# ATmega328p-DHT11-DS1307-LCD-StripBd.net
KiCad netlist of a schematic drawn in EAGLE
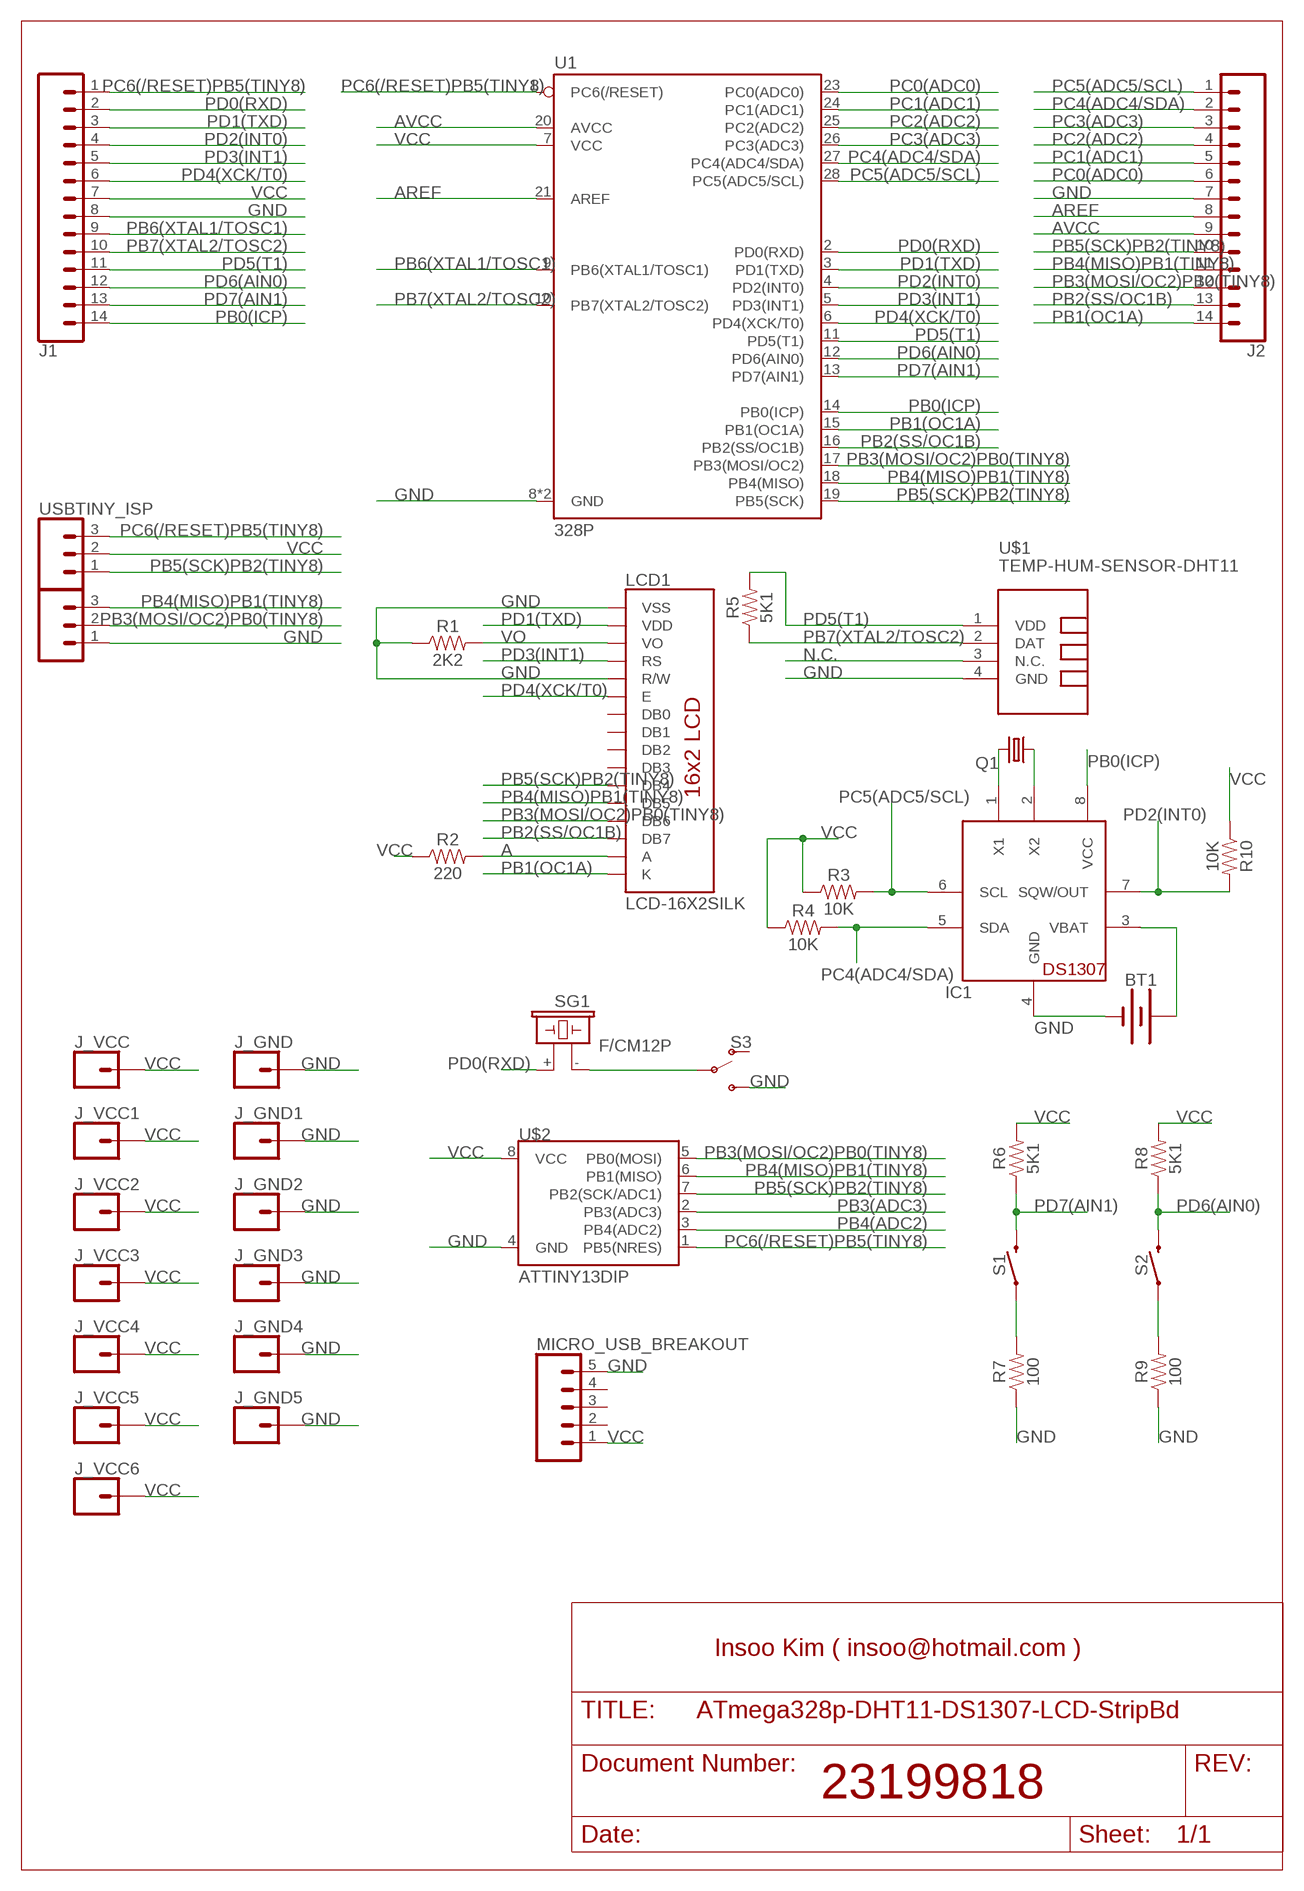
[diagram p0: schematic, sheet 1]

(export (version "E")
  (design (tool "Eeschema 10.0.6"))
  (components
    (comp (ref "BT1")
      (value "BATTERY-20MM_PTH")
      (footprint "eagle-import:BATTCOM_20MM_PTH")
      (libsource (lib "eagle-import") (part "BATTERY-20MM_PTH"))
    )
    (comp (ref "IC1")
      (value "DS1307")
      (footprint "eagle-import:DIL08")
      (libsource (lib "eagle-import") (part "DS1307"))
    )
    (comp (ref "J1")
      (value "CONN_14")
      (footprint "eagle-import:1X14")
      (libsource (lib "eagle-import") (part "CONN_14"))
    )
    (comp (ref "J2")
      (value "CONN_14")
      (footprint "eagle-import:1X14")
      (libsource (lib "eagle-import") (part "CONN_14"))
    )
    (comp (ref "J3")
      (value "455-1750-1-ND")
      (footprint "eagle-import:1X03")
      (libsource (lib "eagle-import") (part "CONN_03"))
    )
    (comp (ref "J_GND")
      (value "CONN_01")
      (footprint "eagle-import:1X01")
      (libsource (lib "eagle-import") (part "CONN_01"))
    )
    (comp (ref "J_GND1")
      (value "CONN_01")
      (footprint "eagle-import:1X01")
      (libsource (lib "eagle-import") (part "CONN_01"))
    )
    (comp (ref "J_GND2")
      (value "CONN_01")
      (footprint "eagle-import:1X01")
      (libsource (lib "eagle-import") (part "CONN_01"))
    )
    (comp (ref "J_GND3")
      (value "CONN_01")
      (footprint "eagle-import:1X01")
      (libsource (lib "eagle-import") (part "CONN_01"))
    )
    (comp (ref "J_GND4")
      (value "CONN_01")
      (footprint "eagle-import:1X01")
      (libsource (lib "eagle-import") (part "CONN_01"))
    )
    (comp (ref "J_GND5")
      (value "CONN_01")
      (footprint "eagle-import:1X01")
      (libsource (lib "eagle-import") (part "CONN_01"))
    )
    (comp (ref "J_VCC")
      (value "CONN_01")
      (footprint "eagle-import:1X01")
      (libsource (lib "eagle-import") (part "CONN_01"))
    )
    (comp (ref "J_VCC1")
      (value "CONN_01")
      (footprint "eagle-import:1X01")
      (libsource (lib "eagle-import") (part "CONN_01"))
    )
    (comp (ref "J_VCC2")
      (value "CONN_01")
      (footprint "eagle-import:1X01")
      (libsource (lib "eagle-import") (part "CONN_01"))
    )
    (comp (ref "J_VCC3")
      (value "CONN_01")
      (footprint "eagle-import:1X01")
      (libsource (lib "eagle-import") (part "CONN_01"))
    )
    (comp (ref "J_VCC4")
      (value "CONN_01")
      (footprint "eagle-import:1X01")
      (libsource (lib "eagle-import") (part "CONN_01"))
    )
    (comp (ref "J_VCC5")
      (value "CONN_01")
      (footprint "eagle-import:1X01")
      (libsource (lib "eagle-import") (part "CONN_01"))
    )
    (comp (ref "J_VCC6")
      (value "CONN_01")
      (footprint "eagle-import:1X01")
      (libsource (lib "eagle-import") (part "CONN_01"))
    )
    (comp (ref "LCD1")
      (value "LCD-16X2SILK")
      (footprint "eagle-import:LCD-16X2")
      (libsource (lib "eagle-import") (part "LCD-16X2SILK"))
    )
    (comp (ref "MICRO_USB_BREAKOUT")
      (value "CONN_05")
      (footprint "eagle-import:1X05")
      (libsource (lib "eagle-import") (part "CONN_05"))
    )
    (comp (ref "Q1")
      (value "CRYSTALTC26H")
      (footprint "eagle-import:TC26H")
      (libsource (lib "eagle-import") (part "CRYSTALTC26H"))
    )
    (comp (ref "R1")
      (value "2K2")
      (footprint "eagle-import:AXIAL-0.3")
      (libsource (lib "eagle-import") (part "1KOHM-HORIZ-1/4W-5%"))
    )
    (comp (ref "R2")
      (value "220")
      (footprint "eagle-import:AXIAL-0.3")
      (libsource (lib "eagle-import") (part "1KOHM-HORIZ-1/4W-5%"))
    )
    (comp (ref "R3")
      (value "10K")
      (footprint "eagle-import:AXIAL-0.3")
      (libsource (lib "eagle-import") (part "1KOHM-HORIZ-1/4W-5%"))
    )
    (comp (ref "R4")
      (value "10K")
      (footprint "eagle-import:AXIAL-0.3")
      (libsource (lib "eagle-import") (part "1KOHM-HORIZ-1/4W-5%"))
    )
    (comp (ref "R5")
      (value "5K1")
      (footprint "eagle-import:AXIAL-0.3")
      (libsource (lib "eagle-import") (part "1KOHM-HORIZ-1/4W-5%"))
    )
    (comp (ref "R6")
      (value "5K1")
      (footprint "eagle-import:AXIAL-0.3")
      (libsource (lib "eagle-import") (part "1KOHM-HORIZ-1/4W-5%"))
    )
    (comp (ref "R7")
      (value "100")
      (footprint "eagle-import:AXIAL-0.3")
      (libsource (lib "eagle-import") (part "1KOHM-HORIZ-1/4W-5%"))
    )
    (comp (ref "R8")
      (value "5K1")
      (footprint "eagle-import:AXIAL-0.3")
      (libsource (lib "eagle-import") (part "1KOHM-HORIZ-1/4W-5%"))
    )
    (comp (ref "R9")
      (value "100")
      (footprint "eagle-import:AXIAL-0.3")
      (libsource (lib "eagle-import") (part "1KOHM-HORIZ-1/4W-5%"))
    )
    (comp (ref "R10")
      (value "10K")
      (footprint "eagle-import:AXIAL-0.3")
      (libsource (lib "eagle-import") (part "1KOHM-HORIZ-1/4W-5%"))
    )
    (comp (ref "S1")
      (value "MOMENTARY-SWITCH-SPST-PTH-12MM")
      (footprint "eagle-import:TACTILE_SWITCH_PTH_12MM")
      (libsource (lib "eagle-import") (part "MOMENTARY-SWITCH-SPST-PTH-12MM"))
    )
    (comp (ref "S2")
      (value "MOMENTARY-SWITCH-SPST-PTH-12MM")
      (footprint "eagle-import:TACTILE_SWITCH_PTH_12MM")
      (libsource (lib "eagle-import") (part "MOMENTARY-SWITCH-SPST-PTH-12MM"))
    )
    (comp (ref "S3")
      (value "SWITCH-SPDT-PTH-11.6X4.0MM")
      (footprint "eagle-import:SWITCH_SPDT_PTH_11.6X4.0MM")
      (libsource (lib "eagle-import") (part "SWITCH-SPDT-PTH-11.6X4.0MM"))
    )
    (comp (ref "SG1")
      (value "F/CM12P")
      (footprint "eagle-import:F_CM12P")
      (libsource (lib "eagle-import") (part "F/CM12P"))
    )
    (comp (ref "U$1")
      (value "TEMP-HUM-SENSOR-DHT11")
      (footprint "eagle-import:TEMP-HUM-SENSOR-DHT11")
      (libsource (lib "eagle-import") (part "TEMP-HUM-SENSOR-DHT11"))
    )
    (comp (ref "U$2")
      (value "ATTINY13DIP")
      (footprint "eagle-import:DIP08_MCU")
      (libsource (lib "eagle-import") (part "ATTINY13DIP"))
    )
    (comp (ref "U1")
      (value "328P")
      (footprint "eagle-import:DIP28")
      (libsource (lib "eagle-import") (part "ATMEGA328P_PDIP"))
    )
    (comp (ref "USBTINY_ISP")
      (value "455-1750-1-ND")
      (footprint "eagle-import:1X03")
      (libsource (lib "eagle-import") (part "CONN_03"))
    )
  )
  (nets
    (net (code "1") (name "/A") (class "Default")
      (node (ref "LCD1") (pin "15") (pinfunction "A_15") (pintype "power_in"))
      (node (ref "R2") (pin "P$2") (pinfunction "2_P$2") (pintype "passive"))
    )
    (net (code "2") (name "/AREF") (class "Default")
      (node (ref "J2") (pin "8") (pinfunction "8_8") (pintype "passive"))
      (node (ref "U1") (pin "21") (pinfunction "AREF_21") (pintype "bidirectional"))
    )
    (net (code "3") (name "/AVCC") (class "Default")
      (node (ref "J2") (pin "9") (pinfunction "9_9") (pintype "passive"))
      (node (ref "U1") (pin "20") (pinfunction "AVCC_20") (pintype "bidirectional"))
    )
    (net (code "4") (name "/GND") (class "Default")
      (node (ref "BT1") (pin "2") (pinfunction "-_2") (pintype "power_in"))
      (node (ref "IC1") (pin "4") (pinfunction "GND_4") (pintype "power_in"))
      (node (ref "J1") (pin "8") (pinfunction "8_8") (pintype "passive"))
      (node (ref "J2") (pin "7") (pinfunction "7_7") (pintype "passive"))
      (node (ref "J3") (pin "1") (pinfunction "1_1") (pintype "passive"))
      (node (ref "J_GND") (pin "1") (pinfunction "1_1") (pintype "passive"))
      (node (ref "J_GND1") (pin "1") (pinfunction "1_1") (pintype "passive"))
      (node (ref "J_GND2") (pin "1") (pinfunction "1_1") (pintype "passive"))
      (node (ref "J_GND3") (pin "1") (pinfunction "1_1") (pintype "passive"))
      (node (ref "J_GND4") (pin "1") (pinfunction "1_1") (pintype "passive"))
      (node (ref "J_GND5") (pin "1") (pinfunction "1_1") (pintype "passive"))
      (node (ref "LCD1") (pin "1") (pinfunction "VSS_1") (pintype "power_in"))
      (node (ref "LCD1") (pin "5") (pinfunction "R/W_5") (pintype "input"))
      (node (ref "MICRO_USB_BREAKOUT") (pin "5") (pinfunction "5_5") (pintype "passive"))
      (node (ref "R1") (pin "P$1") (pinfunction "1_P$1") (pintype "passive"))
      (node (ref "R7") (pin "P$1") (pinfunction "1_P$1") (pintype "passive"))
      (node (ref "R9") (pin "P$1") (pinfunction "1_P$1") (pintype "passive"))
      (node (ref "S3") (pin "3") (pinfunction "S_3") (pintype "passive"))
      (node (ref "U$1") (pin "4") (pinfunction "GND_4") (pintype "power_in"))
      (node (ref "U$2") (pin "4") (pinfunction "GND_4") (pintype "bidirectional"))
      (node (ref "U1") (pin "22") (pinfunction "GND_22") (pintype "bidirectional"))
      (node (ref "U1") (pin "8") (pinfunction "GND_8") (pintype "bidirectional"))
    )
    (net (code "5") (name "/N.C.") (class "Default")
      (node (ref "U$1") (pin "3") (pinfunction "N.C._3") (pintype "passive"))
    )
    (net (code "6") (name "/PB0(ICP)") (class "Default")
      (node (ref "IC1") (pin "8") (pinfunction "VCC_8") (pintype "power_in"))
      (node (ref "J1") (pin "14") (pinfunction "14_14") (pintype "passive"))
      (node (ref "U1") (pin "14") (pinfunction "PB0(ICP)_14") (pintype "bidirectional"))
    )
    (net (code "7") (name "/PB1(OC1A)") (class "Default")
      (node (ref "J2") (pin "14") (pinfunction "14_14") (pintype "passive"))
      (node (ref "LCD1") (pin "16") (pinfunction "K_16") (pintype "power_in"))
      (node (ref "U1") (pin "15") (pinfunction "PB1(OC1A)_15") (pintype "bidirectional"))
    )
    (net (code "8") (name "/PB2(SS{slash}OC1B)") (class "Default")
      (node (ref "J2") (pin "13") (pinfunction "13_13") (pintype "passive"))
      (node (ref "LCD1") (pin "14") (pinfunction "DB7_14") (pintype "bidirectional"))
      (node (ref "U1") (pin "16") (pinfunction "PB2(SS/OC1B)_16") (pintype "bidirectional"))
    )
    (net (code "9") (name "/PB3(ADC3)") (class "Default")
      (node (ref "U$2") (pin "2") (pinfunction "PB3(ADC3)_2") (pintype "bidirectional"))
    )
    (net (code "10") (name "/PB3(MOSI{slash}OC2)PB0(TINY8)") (class "Default")
      (node (ref "J2") (pin "12") (pinfunction "12_12") (pintype "passive"))
      (node (ref "J3") (pin "2") (pinfunction "2_2") (pintype "passive"))
      (node (ref "LCD1") (pin "13") (pinfunction "DB6_13") (pintype "bidirectional"))
      (node (ref "U$2") (pin "5") (pinfunction "PB0(MOSI)_5") (pintype "bidirectional"))
      (node (ref "U1") (pin "17") (pinfunction "PB3(MOSI/OC2)_17") (pintype "bidirectional"))
    )
    (net (code "11") (name "/PB4(ADC2)") (class "Default")
      (node (ref "U$2") (pin "3") (pinfunction "PB4(ADC2)_3") (pintype "bidirectional"))
    )
    (net (code "12") (name "/PB4(MISO)PB1(TINY8)") (class "Default")
      (node (ref "J2") (pin "11") (pinfunction "11_11") (pintype "passive"))
      (node (ref "J3") (pin "3") (pinfunction "3_3") (pintype "passive"))
      (node (ref "LCD1") (pin "12") (pinfunction "DB5_12") (pintype "bidirectional"))
      (node (ref "U$2") (pin "6") (pinfunction "PB1(MISO)_6") (pintype "bidirectional"))
      (node (ref "U1") (pin "18") (pinfunction "PB4(MISO)_18") (pintype "bidirectional"))
    )
    (net (code "13") (name "/PB5(SCK)PB2(TINY8)") (class "Default")
      (node (ref "J2") (pin "10") (pinfunction "10_10") (pintype "passive"))
      (node (ref "LCD1") (pin "11") (pinfunction "DB4_11") (pintype "bidirectional"))
      (node (ref "U$2") (pin "7") (pinfunction "PB2(SCK/ADC1)_7") (pintype "bidirectional"))
      (node (ref "U1") (pin "19") (pinfunction "PB5(SCK)_19") (pintype "bidirectional"))
      (node (ref "USBTINY_ISP") (pin "1") (pinfunction "1_1") (pintype "passive"))
    )
    (net (code "14") (name "/PB6(XTAL1{slash}TOSC1)") (class "Default")
      (node (ref "J1") (pin "9") (pinfunction "9_9") (pintype "passive"))
      (node (ref "U1") (pin "9") (pinfunction "PB6(XTAL1/TOSC1)_9") (pintype "bidirectional"))
    )
    (net (code "15") (name "/PB7(XTAL2{slash}TOSC2)") (class "Default")
      (node (ref "J1") (pin "10") (pinfunction "10_10") (pintype "passive"))
      (node (ref "R5") (pin "P$1") (pinfunction "1_P$1") (pintype "passive"))
      (node (ref "U$1") (pin "2") (pinfunction "DAT_2") (pintype "bidirectional"))
      (node (ref "U1") (pin "10") (pinfunction "PB7(XTAL2/TOSC2)_10") (pintype "bidirectional"))
    )
    (net (code "16") (name "/PC0(ADC0)") (class "Default")
      (node (ref "J2") (pin "6") (pinfunction "6_6") (pintype "passive"))
      (node (ref "U1") (pin "23") (pinfunction "PC0(ADC0)_23") (pintype "bidirectional"))
    )
    (net (code "17") (name "/PC1(ADC1)") (class "Default")
      (node (ref "J2") (pin "5") (pinfunction "5_5") (pintype "passive"))
      (node (ref "U1") (pin "24") (pinfunction "PC1(ADC1)_24") (pintype "bidirectional"))
    )
    (net (code "18") (name "/PC2(ADC2)") (class "Default")
      (node (ref "J2") (pin "4") (pinfunction "4_4") (pintype "passive"))
      (node (ref "U1") (pin "25") (pinfunction "PC2(ADC2)_25") (pintype "bidirectional"))
    )
    (net (code "19") (name "/PC3(ADC3)") (class "Default")
      (node (ref "J2") (pin "3") (pinfunction "3_3") (pintype "passive"))
      (node (ref "U1") (pin "26") (pinfunction "PC3(ADC3)_26") (pintype "bidirectional"))
    )
    (net (code "20") (name "/PC4(ADC4{slash}SDA)") (class "Default")
      (node (ref "IC1") (pin "5") (pinfunction "SDA_5") (pintype "bidirectional"))
      (node (ref "J2") (pin "2") (pinfunction "2_2") (pintype "passive"))
      (node (ref "R4") (pin "P$2") (pinfunction "2_P$2") (pintype "passive"))
      (node (ref "U1") (pin "27") (pinfunction "PC4(ADC4/SDA)_27") (pintype "bidirectional"))
    )
    (net (code "21") (name "/PC5(ADC5{slash}SCL)") (class "Default")
      (node (ref "IC1") (pin "6") (pinfunction "SCL_6") (pintype "bidirectional"))
      (node (ref "J2") (pin "1") (pinfunction "1_1") (pintype "passive"))
      (node (ref "R3") (pin "P$2") (pinfunction "2_P$2") (pintype "passive"))
      (node (ref "U1") (pin "28") (pinfunction "PC5(ADC5/SCL)_28") (pintype "bidirectional"))
    )
    (net (code "22") (name "/PC6({slash}RESET)PB5(TINY8)") (class "Default")
      (node (ref "J1") (pin "1") (pinfunction "1_1") (pintype "passive"))
      (node (ref "U$2") (pin "1") (pinfunction "PB5(NRES)_1") (pintype "bidirectional"))
      (node (ref "U1") (pin "1") (pinfunction "PC6(/RESET)_1") (pintype "bidirectional"))
      (node (ref "USBTINY_ISP") (pin "3") (pinfunction "3_3") (pintype "passive"))
    )
    (net (code "23") (name "/PD0(RXD)") (class "Default")
      (node (ref "J1") (pin "2") (pinfunction "2_2") (pintype "passive"))
      (node (ref "SG1") (pin "+") (pinfunction "1_+") (pintype "passive"))
      (node (ref "U1") (pin "2") (pinfunction "PD0(RXD)_2") (pintype "bidirectional"))
    )
    (net (code "24") (name "/PD1(TXD)") (class "Default")
      (node (ref "J1") (pin "3") (pinfunction "3_3") (pintype "passive"))
      (node (ref "LCD1") (pin "2") (pinfunction "VDD_2") (pintype "power_in"))
      (node (ref "U1") (pin "3") (pinfunction "PD1(TXD)_3") (pintype "bidirectional"))
    )
    (net (code "25") (name "/PD2(INT0)") (class "Default")
      (node (ref "IC1") (pin "7") (pinfunction "SQW/OUT_7") (pintype "bidirectional"))
      (node (ref "J1") (pin "4") (pinfunction "4_4") (pintype "passive"))
      (node (ref "R10") (pin "P$2") (pinfunction "2_P$2") (pintype "passive"))
      (node (ref "U1") (pin "4") (pinfunction "PD2(INT0)_4") (pintype "bidirectional"))
    )
    (net (code "26") (name "/PD3(INT1)") (class "Default")
      (node (ref "J1") (pin "5") (pinfunction "5_5") (pintype "passive"))
      (node (ref "LCD1") (pin "4") (pinfunction "RS_4") (pintype "input"))
      (node (ref "U1") (pin "5") (pinfunction "PD3(INT1)_5") (pintype "bidirectional"))
    )
    (net (code "27") (name "/PD4(XCK{slash}T0)") (class "Default")
      (node (ref "J1") (pin "6") (pinfunction "6_6") (pintype "passive"))
      (node (ref "LCD1") (pin "6") (pinfunction "E_6") (pintype "input"))
      (node (ref "U1") (pin "6") (pinfunction "PD4(XCK/T0)_6") (pintype "bidirectional"))
    )
    (net (code "28") (name "/PD5(T1)") (class "Default")
      (node (ref "J1") (pin "11") (pinfunction "11_11") (pintype "passive"))
      (node (ref "R5") (pin "P$2") (pinfunction "2_P$2") (pintype "passive"))
      (node (ref "U$1") (pin "1") (pinfunction "VDD_1") (pintype "power_in"))
      (node (ref "U1") (pin "11") (pinfunction "PD5(T1)_11") (pintype "bidirectional"))
    )
    (net (code "29") (name "/PD6(AIN0)") (class "Default")
      (node (ref "J1") (pin "12") (pinfunction "12_12") (pintype "passive"))
      (node (ref "R8") (pin "P$1") (pinfunction "1_P$1") (pintype "passive"))
      (node (ref "S2") (pin "3") (pinfunction "2_3") (pintype "passive"))
      (node (ref "U1") (pin "12") (pinfunction "PD6(AIN0)_12") (pintype "bidirectional"))
    )
    (net (code "30") (name "/PD7(AIN1)") (class "Default")
      (node (ref "J1") (pin "13") (pinfunction "13_13") (pintype "passive"))
      (node (ref "R6") (pin "P$1") (pinfunction "1_P$1") (pintype "passive"))
      (node (ref "S1") (pin "3") (pinfunction "2_3") (pintype "passive"))
      (node (ref "U1") (pin "13") (pinfunction "PD7(AIN1)_13") (pintype "bidirectional"))
    )
    (net (code "31") (name "/VCC") (class "Default")
      (node (ref "J1") (pin "7") (pinfunction "7_7") (pintype "passive"))
      (node (ref "J_VCC") (pin "1") (pinfunction "1_1") (pintype "passive"))
      (node (ref "J_VCC1") (pin "1") (pinfunction "1_1") (pintype "passive"))
      (node (ref "J_VCC2") (pin "1") (pinfunction "1_1") (pintype "passive"))
      (node (ref "J_VCC3") (pin "1") (pinfunction "1_1") (pintype "passive"))
      (node (ref "J_VCC4") (pin "1") (pinfunction "1_1") (pintype "passive"))
      (node (ref "J_VCC5") (pin "1") (pinfunction "1_1") (pintype "passive"))
      (node (ref "J_VCC6") (pin "1") (pinfunction "1_1") (pintype "passive"))
      (node (ref "MICRO_USB_BREAKOUT") (pin "1") (pinfunction "1_1") (pintype "passive"))
      (node (ref "R10") (pin "P$1") (pinfunction "1_P$1") (pintype "passive"))
      (node (ref "R2") (pin "P$1") (pinfunction "1_P$1") (pintype "passive"))
      (node (ref "R3") (pin "P$1") (pinfunction "1_P$1") (pintype "passive"))
      (node (ref "R4") (pin "P$1") (pinfunction "1_P$1") (pintype "passive"))
      (node (ref "R6") (pin "P$2") (pinfunction "2_P$2") (pintype "passive"))
      (node (ref "R8") (pin "P$2") (pinfunction "2_P$2") (pintype "passive"))
      (node (ref "U$2") (pin "8") (pinfunction "VCC_8") (pintype "bidirectional"))
      (node (ref "U1") (pin "7") (pinfunction "VCC_7") (pintype "bidirectional"))
      (node (ref "USBTINY_ISP") (pin "2") (pinfunction "2_2") (pintype "passive"))
    )
    (net (code "32") (name "/VO") (class "Default")
      (node (ref "LCD1") (pin "3") (pinfunction "VO_3") (pintype "bidirectional"))
      (node (ref "R1") (pin "P$2") (pinfunction "2_P$2") (pintype "passive"))
    )
    (net (code "33") (name "Net-(BT1-+)") (class "Default")
      (node (ref "BT1") (pin "1") (pinfunction "+_1") (pintype "power_in"))
      (node (ref "IC1") (pin "3") (pinfunction "VBAT_3") (pintype "power_in"))
    )
    (net (code "34") (name "Net-(IC1-X1)") (class "Default")
      (node (ref "IC1") (pin "1") (pinfunction "X1_1") (pintype "passive"))
      (node (ref "Q1") (pin "2") (pinfunction "2_2") (pintype "passive"))
    )
    (net (code "35") (name "Net-(IC1-X2)") (class "Default")
      (node (ref "IC1") (pin "2") (pinfunction "X2_2") (pintype "passive"))
      (node (ref "Q1") (pin "1") (pinfunction "1_1") (pintype "passive"))
    )
    (net (code "36") (name "Net-(R7-2)") (class "Default")
      (node (ref "R7") (pin "P$2") (pinfunction "2_P$2") (pintype "passive"))
      (node (ref "S1") (pin "1") (pinfunction "1_1") (pintype "passive"))
    )
    (net (code "37") (name "Net-(R9-2)") (class "Default")
      (node (ref "R9") (pin "P$2") (pinfunction "2_P$2") (pintype "passive"))
      (node (ref "S2") (pin "1") (pinfunction "1_1") (pintype "passive"))
    )
    (net (code "38") (name "Net-(S3-P)") (class "Default")
      (node (ref "S3") (pin "2") (pinfunction "P_2") (pintype "passive"))
      (node (ref "SG1") (pin "-") (pinfunction "2_-") (pintype "passive"))
    )
    (net (code "39") (name "unconnected-(LCD1-DB0-Pad7)") (class "Default")
      (node (ref "LCD1") (pin "7") (pinfunction "DB0_7") (pintype "bidirectional"))
    )
    (net (code "40") (name "unconnected-(LCD1-DB1-Pad8)") (class "Default")
      (node (ref "LCD1") (pin "8") (pinfunction "DB1_8") (pintype "bidirectional"))
    )
    (net (code "41") (name "unconnected-(LCD1-DB2-Pad9)") (class "Default")
      (node (ref "LCD1") (pin "9") (pinfunction "DB2_9") (pintype "bidirectional"))
    )
    (net (code "42") (name "unconnected-(LCD1-DB3-Pad10)") (class "Default")
      (node (ref "LCD1") (pin "10") (pinfunction "DB3_10") (pintype "bidirectional"))
    )
    (net (code "43") (name "unconnected-(MICRO_USB_BREAKOUT-Pad2)") (class "Default")
      (node (ref "MICRO_USB_BREAKOUT") (pin "2") (pinfunction "2_2") (pintype "passive"))
    )
    (net (code "44") (name "unconnected-(MICRO_USB_BREAKOUT-Pad3)") (class "Default")
      (node (ref "MICRO_USB_BREAKOUT") (pin "3") (pinfunction "3_3") (pintype "passive"))
    )
    (net (code "45") (name "unconnected-(MICRO_USB_BREAKOUT-Pad4)") (class "Default")
      (node (ref "MICRO_USB_BREAKOUT") (pin "4") (pinfunction "4_4") (pintype "passive"))
    )
    (net (code "46") (name "unconnected-(S3-O-Pad1)") (class "Default")
      (node (ref "S3") (pin "1") (pinfunction "O_1") (pintype "passive"))
    )
  )
)
